# XCBMPUSche.net
KiCad netlist of a schematic drawn in Altium Designer
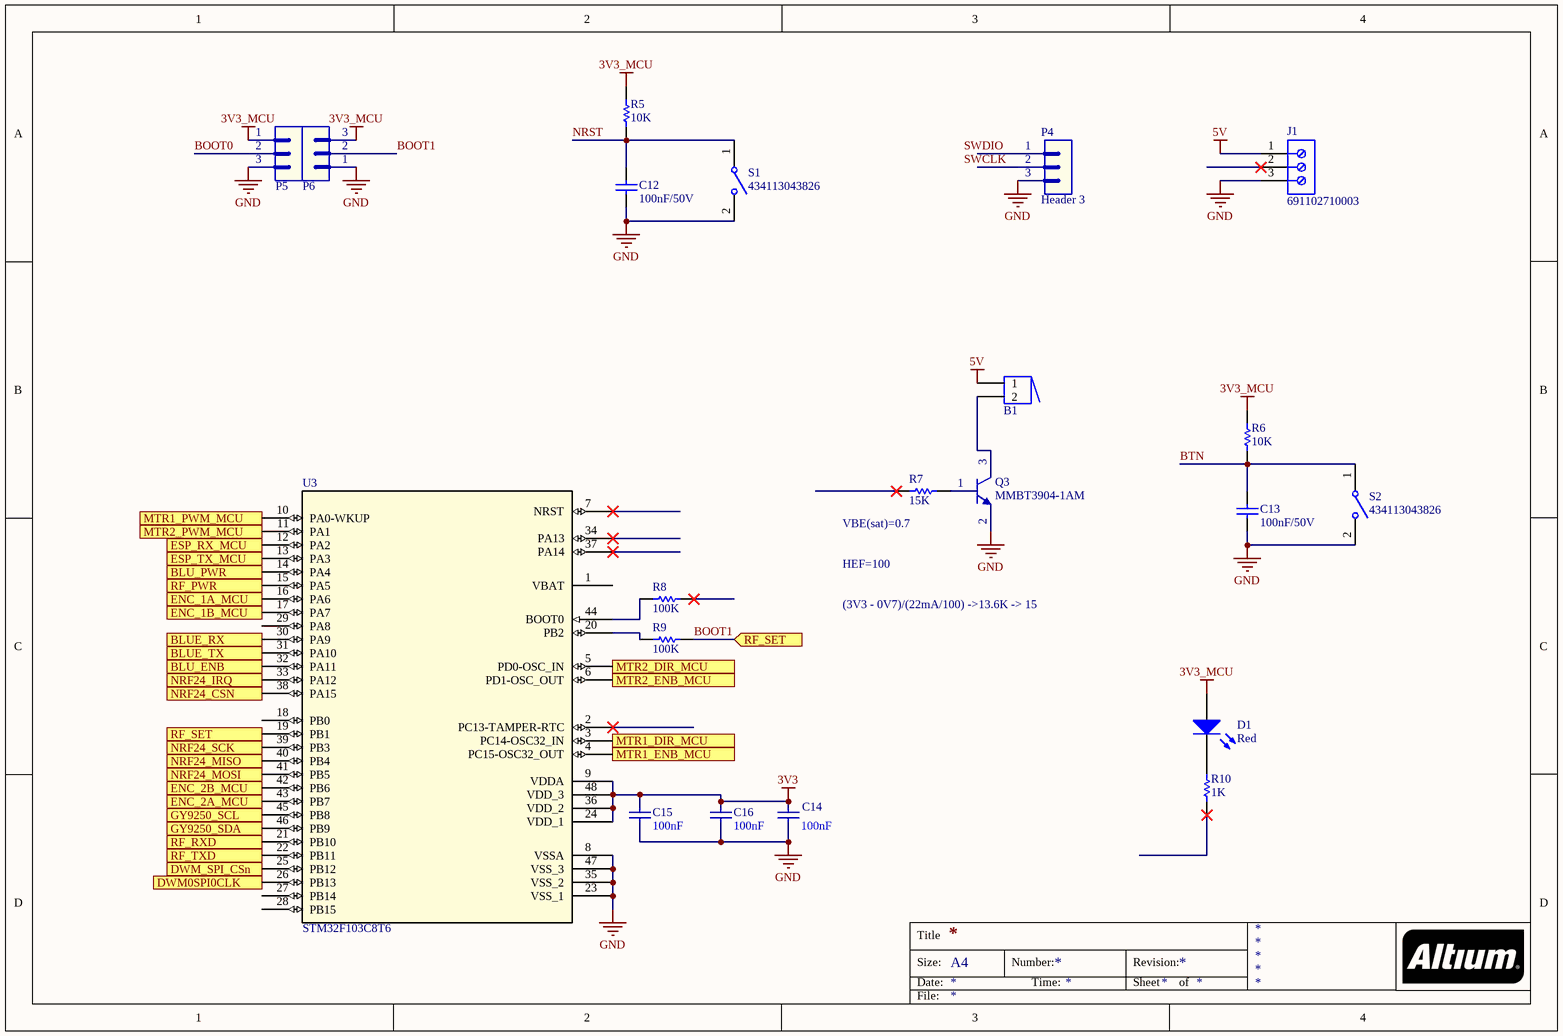
[diagram p0: XCBMPUSche.schdoc]

(export (version "E")
  (design (tool "Eeschema 10.0.6"))
  (components
    (comp (ref "B1")
      (value "Buzzer")
      (footprint "BUZZER")
      (libsource (lib "PIF_Schematic_Lib") (part "Buzzer"))
    )
    (comp (ref "C12")
      (value "100nF/50V")
      (footprint "CAP-SM-0805")
      (description "CAP CER 0.1UF 50V Y5V 0805")
      (fields
        (field (name "MANUFACTURER") "Samsung Electro-Mechanics")
        (field (name "MANUFACTURER PART NUMBER") "CL21F104ZBCNNNC")
      )
      (libsource (lib "Capacitor") (part "Cap-100nF-50V-0805"))
    )
    (comp (ref "C13")
      (value "100nF/50V")
      (footprint "CAP-SM-0805")
      (description "CAP CER 0.1UF 50V Y5V 0805")
      (fields
        (field (name "MANUFACTURER") "Samsung Electro-Mechanics")
        (field (name "MANUFACTURER PART NUMBER") "CL21F104ZBCNNNC")
      )
      (libsource (lib "Capacitor") (part "Cap-100nF-50V-0805"))
    )
    (comp (ref "C14")
      (value "100nF")
      (footprint "CN1")
      (description "Capacitor")
      (fields (field (name "Comment") "Cap Non-Pol"))
      (libsource (lib "Capacitor-TH") (part "Cap-TH-NonPol"))
    )
    (comp (ref "C15")
      (value "100nF")
      (footprint "CN1")
      (description "Capacitor")
      (fields (field (name "Comment") "Cap Non-Pol"))
      (libsource (lib "Capacitor-TH") (part "Cap-TH-NonPol"))
    )
    (comp (ref "C16")
      (value "100nF")
      (footprint "CN1")
      (description "Capacitor")
      (fields (field (name "Comment") "Cap Non-Pol"))
      (libsource (lib "Capacitor-TH") (part "Cap-TH-NonPol"))
    )
    (comp (ref "D1")
      (value "Red")
      (footprint "LED-3mm")
      (description "LED RED CLEAR T-1 T/H")
      (fields
        (field (name "MANUFACTURER") "Kingbright")
        (field (name "MANUFACTURER PART NUMBER") "WP710A10SEC/J3")
      )
      (libsource (lib "LED") (part "LED-RED-TH-3mm"))
    )
    (comp (ref "J1")
      (value "691102710003")
      (footprint "691102710003")
      (description "WR-TBL Serie 102 Horizontal Entry Modular, Pressure Clamp, pitch 5mm, 3p")
      (fields (field (name "PUBLISHER") "Wurth Elektronik"))
      (libsource (lib "691101710002_Altium_WR-TBL_rev19a") (part "691102710003"))
    )
    (comp (ref "P4")
      (value "Header 3")
      (footprint "JP3")
      (description "Header, 3-Pin")
      (fields (field (name "PUBLISHER") "Altium Limited"))
      (libsource (lib "") (part "Header 3_1"))
    )
    (comp (ref "P5")
      (value "Header 3")
      (footprint "JP3")
      (description "Header, 3-Pin")
      (fields (field (name "PUBLISHER") "Altium Limited"))
      (libsource (lib "") (part "Header 3_1"))
    )
    (comp (ref "P6")
      (value "Header 3")
      (footprint "JP3")
      (description "Header, 3-Pin")
      (fields (field (name "PUBLISHER") "Altium Limited"))
      (libsource (lib "PIF_C16_lib") (part "Header 3"))
    )
    (comp (ref "Q3")
      (value "MMBT3904-1AM")
      (footprint "SOT23_NEX")
      (libsource (lib "BJT") (part "MMBT3904-1AM"))
    )
    (comp (ref "R5")
      (value "10K")
      (footprint "Resistor:RES-SM-0805")
      (description "RES 10K OHM 1% 1/4W 0805")
      (fields
        (field (name "MANUFACTURER") "Stackpole Electronics Inc")
        (field (name "MANUFACTURER PART NUMBER") "RNCP0805FTD10K0")
      )
      (libsource (lib "Resistor") (part "Res-10k-0805"))
    )
    (comp (ref "R6")
      (value "10K")
      (footprint "Resistor:RES-SM-0805")
      (description "RES 10K OHM 1% 1/4W 0805")
      (fields
        (field (name "MANUFACTURER") "Stackpole Electronics Inc")
        (field (name "MANUFACTURER PART NUMBER") "RNCP0805FTD10K0")
      )
      (libsource (lib "Resistor") (part "Res-10k-0805"))
    )
    (comp (ref "R7")
      (value "15K")
      (footprint "Resistor:RES-SM-0805")
      (description "RES 15K OHM 1% 1/4W 0805")
      (fields
        (field (name "MANUFACTURER") "TE Connectivity Passive Product")
        (field (name "MANUFACTURER PART NUMBER") "CRGCQ0805F15K")
      )
      (libsource (lib "Resistor") (part "Res-15K-0805"))
    )
    (comp (ref "R8")
      (value "100K")
      (footprint "Resistor:RES-SM-0805")
      (description "RES 0 OHM JUMPER 0805")
      (fields
        (field (name "MANUFACTURER") "Vishay Dale")
        (field (name "MANUFACTURER PART NUMBER") "WSL080500000ZEA9")
      )
      (libsource (lib "Resistor") (part "Res-100K-0805"))
    )
    (comp (ref "R9")
      (value "100K")
      (footprint "Resistor:RES-SM-0805")
      (description "RES 0 OHM JUMPER 0805")
      (fields
        (field (name "MANUFACTURER") "Vishay Dale")
        (field (name "MANUFACTURER PART NUMBER") "WSL080500000ZEA9")
      )
      (libsource (lib "Resistor") (part "Res-100K-0805"))
    )
    (comp (ref "R10")
      (value "1K")
      (footprint "Resistor:RES-SM-0805")
      (description "RES 1K OHM 1% 1/4W 0805")
      (fields
        (field (name "MANUFACTURER") "Stackpole Electronics Inc")
        (field (name "MANUFACTURER PART NUMBER") "RNCP0805FTD1K00")
      )
      (libsource (lib "Resistor") (part "Res-1K-0805"))
    )
    (comp (ref "S1")
      (value "434113043826")
      (footprint "434113043826")
      (description "WS-TASV J-Bend SMT Tact Switch 6x3.5mm, height 4.3mm, 260gf")
      (fields (field (name "PUBLISHER") "Wurth Elektronik"))
      (libsource (lib "434113043826_Altium_WS-TASV_rev20a") (part "434113043826"))
    )
    (comp (ref "S2")
      (value "434113043826")
      (footprint "434113043826")
      (description "WS-TASV J-Bend SMT Tact Switch 6x3.5mm, height 4.3mm, 260gf")
      (fields (field (name "PUBLISHER") "Wurth Elektronik"))
      (libsource (lib "434113043826_Altium_WS-TASV_rev20a") (part "434113043826"))
    )
    (comp (ref "U3")
      (value "STM32F103C8T6")
      (footprint "STM32F103C8T6")
      (description "No Description Available")
      (fields (field (name "COPYRIGHT") "Copyright (C) 2018 Accelerated Designs. All rights reserved"))
      (libsource (lib "Bai1") (part "STM32F103C8T6"))
    )
  )
  (nets
    (net (code "1") (name "/BLUE_RX") (class "Default")
      (node (ref "U3") (pin "30") (pinfunction "PA9_30") (pintype "bidirectional"))
    )
    (net (code "2") (name "/BLUE_TX") (class "Default")
      (node (ref "U3") (pin "31") (pinfunction "PA10_31") (pintype "bidirectional"))
    )
    (net (code "3") (name "/BLU_ENB") (class "Default")
      (node (ref "U3") (pin "32") (pinfunction "PA11_32") (pintype "bidirectional"))
    )
    (net (code "4") (name "/BLU_PWR") (class "Default")
      (node (ref "U3") (pin "14") (pinfunction "PA4_14") (pintype "bidirectional"))
    )
    (net (code "5") (name "/BOOT0") (class "Default")
      (node (ref "P5") (pin "2") (pinfunction "2_2") (pintype "passive"))
    )
    (net (code "6") (name "/BOOT1") (class "Default")
      (node (ref "P6") (pin "2") (pinfunction "2_2") (pintype "passive"))
      (node (ref "R9") (pin "2") (pinfunction "2_2") (pintype "passive"))
      (node (ref "U3") (pin "19") (pinfunction "PB1_19") (pintype "bidirectional"))
    )
    (net (code "7") (name "/BTN") (class "Default")
      (node (ref "C13") (pin "2") (pinfunction "2_2") (pintype "passive"))
      (node (ref "R6") (pin "1") (pinfunction "1_1") (pintype "passive"))
      (node (ref "S2") (pin "1") (pinfunction "1_1") (pintype "passive"))
    )
    (net (code "8") (name "/DWM0SPI0CLK") (class "Default")
      (node (ref "U3") (pin "26") (pinfunction "PB13_26") (pintype "bidirectional"))
    )
    (net (code "9") (name "/DWM_SPI_CSn") (class "Default")
      (node (ref "U3") (pin "25") (pinfunction "PB12_25") (pintype "bidirectional"))
    )
    (net (code "10") (name "/ENC_1A_MCU") (class "Default")
      (node (ref "U3") (pin "16") (pinfunction "PA6_16") (pintype "bidirectional"))
    )
    (net (code "11") (name "/ENC_1B_MCU") (class "Default")
      (node (ref "U3") (pin "17") (pinfunction "PA7_17") (pintype "bidirectional"))
    )
    (net (code "12") (name "/ENC_2A_MCU") (class "Default")
      (node (ref "U3") (pin "43") (pinfunction "PB7_43") (pintype "bidirectional"))
    )
    (net (code "13") (name "/ENC_2B_MCU") (class "Default")
      (node (ref "U3") (pin "42") (pinfunction "PB6_42") (pintype "bidirectional"))
    )
    (net (code "14") (name "/ESP_RX_MCU") (class "Default")
      (node (ref "U3") (pin "12") (pinfunction "PA2_12") (pintype "bidirectional"))
    )
    (net (code "15") (name "/ESP_TX_MCU") (class "Default")
      (node (ref "U3") (pin "13") (pinfunction "PA3_13") (pintype "bidirectional"))
    )
    (net (code "16") (name "/GY9250_SCL") (class "Default")
      (node (ref "U3") (pin "45") (pinfunction "PB8_45") (pintype "bidirectional"))
    )
    (net (code "17") (name "/GY9250_SDA") (class "Default")
      (node (ref "U3") (pin "46") (pinfunction "PB9_46") (pintype "bidirectional"))
    )
    (net (code "18") (name "/MTR1_DIR_MCU") (class "Default")
      (node (ref "U3") (pin "3") (pinfunction "PC14-OSC32_IN_3") (pintype "bidirectional"))
    )
    (net (code "19") (name "/MTR1_ENB_MCU") (class "Default")
      (node (ref "U3") (pin "4") (pinfunction "PC15-OSC32_OUT_4") (pintype "bidirectional"))
    )
    (net (code "20") (name "/MTR1_PWM_MCU") (class "Default")
      (node (ref "U3") (pin "10") (pinfunction "PA0-WKUP_10") (pintype "bidirectional"))
    )
    (net (code "21") (name "/MTR2_DIR_MCU") (class "Default")
      (node (ref "U3") (pin "5") (pinfunction "PD0-OSC_IN_5") (pintype "bidirectional"))
    )
    (net (code "22") (name "/MTR2_ENB_MCU") (class "Default")
      (node (ref "U3") (pin "6") (pinfunction "PD1-OSC_OUT_6") (pintype "bidirectional"))
    )
    (net (code "23") (name "/MTR2_PWM_MCU") (class "Default")
      (node (ref "U3") (pin "11") (pinfunction "PA1_11") (pintype "bidirectional"))
    )
    (net (code "24") (name "/NRF24_CSN") (class "Default")
      (node (ref "U3") (pin "38") (pinfunction "PA15_38") (pintype "bidirectional"))
    )
    (net (code "25") (name "/NRF24_IRQ") (class "Default")
      (node (ref "U3") (pin "33") (pinfunction "PA12_33") (pintype "bidirectional"))
    )
    (net (code "26") (name "/NRF24_MISO") (class "Default")
      (node (ref "U3") (pin "40") (pinfunction "PB4_40") (pintype "bidirectional"))
    )
    (net (code "27") (name "/NRF24_MOSI") (class "Default")
      (node (ref "U3") (pin "41") (pinfunction "PB5_41") (pintype "bidirectional"))
    )
    (net (code "28") (name "/NRF24_SCK") (class "Default")
      (node (ref "U3") (pin "39") (pinfunction "PB3_39") (pintype "bidirectional"))
    )
    (net (code "29") (name "/NRST") (class "Default")
      (node (ref "C12") (pin "2") (pinfunction "2_2") (pintype "passive"))
      (node (ref "R5") (pin "1") (pinfunction "1_1") (pintype "passive"))
      (node (ref "S1") (pin "1") (pinfunction "1_1") (pintype "passive"))
    )
    (net (code "30") (name "/RF_PWR") (class "Default")
      (node (ref "U3") (pin "15") (pinfunction "PA5_15") (pintype "bidirectional"))
    )
    (net (code "31") (name "/RF_RXD") (class "Default")
      (node (ref "U3") (pin "21") (pinfunction "PB10_21") (pintype "bidirectional"))
    )
    (net (code "32") (name "/RF_TXD") (class "Default")
      (node (ref "U3") (pin "22") (pinfunction "PB11_22") (pintype "bidirectional"))
    )
    (net (code "35") (name "3V3") (class "Default")
      (node (ref "C14") (pin "2") (pinfunction "2_2") (pintype "passive"))
      (node (ref "C15") (pin "2") (pinfunction "2_2") (pintype "passive"))
      (node (ref "C16") (pin "2") (pinfunction "2_2") (pintype "passive"))
      (node (ref "U3") (pin "24") (pinfunction "VDD_1_24") (pintype "passive"))
      (node (ref "U3") (pin "36") (pinfunction "VDD_2_36") (pintype "power_in"))
      (node (ref "U3") (pin "48") (pinfunction "VDD_3_48") (pintype "passive"))
      (node (ref "U3") (pin "9") (pinfunction "VDDA_9") (pintype "passive"))
    )
    (net (code "36") (name "3V3_MCU") (class "Default")
      (node (ref "D1") (pin "1") (pinfunction "A_1") (pintype "passive"))
      (node (ref "P5") (pin "1") (pinfunction "1_1") (pintype "passive"))
      (node (ref "P6") (pin "3") (pinfunction "3_3") (pintype "passive"))
      (node (ref "R5") (pin "2") (pinfunction "2_2") (pintype "passive"))
      (node (ref "R6") (pin "2") (pinfunction "2_2") (pintype "passive"))
    )
    (net (code "37") (name "5V") (class "Default")
      (node (ref "B1") (pin "1") (pinfunction "1_1") (pintype "passive"))
      (node (ref "J1") (pin "1") (pinfunction "1_1") (pintype "passive"))
    )
    (net (code "38") (name "GND") (class "Default")
      (node (ref "C12") (pin "1") (pinfunction "1_1") (pintype "passive"))
      (node (ref "C13") (pin "1") (pinfunction "1_1") (pintype "passive"))
      (node (ref "C14") (pin "1") (pinfunction "1_1") (pintype "passive"))
      (node (ref "C15") (pin "1") (pinfunction "1_1") (pintype "passive"))
      (node (ref "C16") (pin "1") (pinfunction "1_1") (pintype "passive"))
      (node (ref "J1") (pin "3") (pinfunction "3_3") (pintype "passive"))
      (node (ref "P4") (pin "3") (pinfunction "3_3") (pintype "passive"))
      (node (ref "P5") (pin "3") (pinfunction "3_3") (pintype "passive"))
      (node (ref "P6") (pin "1") (pinfunction "1_1") (pintype "passive"))
      (node (ref "Q3") (pin "2") (pinfunction "E_2") (pintype "passive"))
      (node (ref "S1") (pin "2") (pinfunction "2_2") (pintype "passive"))
      (node (ref "S2") (pin "2") (pinfunction "2_2") (pintype "passive"))
      (node (ref "U3") (pin "23") (pinfunction "VSS_1_23") (pintype "passive"))
      (node (ref "U3") (pin "35") (pinfunction "VSS_2_35") (pintype "passive"))
      (node (ref "U3") (pin "47") (pinfunction "VSS_3_47") (pintype "passive"))
      (node (ref "U3") (pin "8") (pinfunction "VSSA_8") (pintype "passive"))
    )
    (net (code "39") (name "Net-(D1-K)") (class "Default")
      (node (ref "D1") (pin "2") (pinfunction "K_2") (pintype "passive"))
      (node (ref "R10") (pin "2") (pinfunction "2_2") (pintype "passive"))
    )
    (net (code "40") (name "Net-(Q3-B)") (class "Default")
      (node (ref "Q3") (pin "1") (pinfunction "B_1") (pintype "passive"))
      (node (ref "R7") (pin "2") (pinfunction "2_2") (pintype "passive"))
    )
    (net (code "41") (name "Net-(Q3-C)") (class "Default")
      (node (ref "B1") (pin "2") (pinfunction "2_2") (pintype "passive"))
      (node (ref "Q3") (pin "3") (pinfunction "C_3") (pintype "passive"))
    )
    (net (code "42") (name "Net-(U3-BOOT0)") (class "Default")
      (node (ref "R8") (pin "1") (pinfunction "1_1") (pintype "passive"))
      (node (ref "U3") (pin "44") (pinfunction "BOOT0_44") (pintype "input"))
    )
    (net (code "43") (name "Net-(U3-PB2)") (class "Default")
      (node (ref "R9") (pin "1") (pinfunction "1_1") (pintype "passive"))
      (node (ref "U3") (pin "20") (pinfunction "PB2_20") (pintype "bidirectional"))
    )
    (net (code "44") (name "unconnected-(J1-Pad2)") (class "Default")
      (node (ref "J1") (pin "2") (pinfunction "2_2") (pintype "passive+no_connect"))
    )
    (net (code "45") (name "unconnected-(P4-Pad1)") (class "Default")
      (node (ref "P4") (pin "1") (pinfunction "1_1") (pintype "passive"))
    )
    (net (code "46") (name "unconnected-(P4-Pad2)") (class "Default")
      (node (ref "P4") (pin "2") (pinfunction "2_2") (pintype "passive"))
    )
    (net (code "47") (name "unconnected-(R7-Pad1)") (class "Default")
      (node (ref "R7") (pin "1") (pinfunction "1_1") (pintype "passive+no_connect"))
    )
    (net (code "48") (name "unconnected-(R8-Pad2)") (class "Default")
      (node (ref "R8") (pin "2") (pinfunction "2_2") (pintype "passive+no_connect"))
    )
    (net (code "49") (name "unconnected-(R10-Pad1)") (class "Default")
      (node (ref "R10") (pin "1") (pinfunction "1_1") (pintype "passive+no_connect"))
    )
    (net (code "50") (name "unconnected-(U3-NRST-Pad7)") (class "Default")
      (node (ref "U3") (pin "7") (pinfunction "NRST_7") (pintype "bidirectional+no_connect"))
    )
    (net (code "51") (name "unconnected-(U3-PA8-Pad29)") (class "Default")
      (node (ref "U3") (pin "29") (pinfunction "PA8_29") (pintype "bidirectional"))
    )
    (net (code "52") (name "unconnected-(U3-PA13-Pad34)") (class "Default")
      (node (ref "U3") (pin "34") (pinfunction "PA13_34") (pintype "bidirectional+no_connect"))
    )
    (net (code "53") (name "unconnected-(U3-PA14-Pad37)") (class "Default")
      (node (ref "U3") (pin "37") (pinfunction "PA14_37") (pintype "bidirectional+no_connect"))
    )
    (net (code "54") (name "unconnected-(U3-PB0-Pad18)") (class "Default")
      (node (ref "U3") (pin "18") (pinfunction "PB0_18") (pintype "bidirectional"))
    )
    (net (code "55") (name "unconnected-(U3-PB14-Pad27)") (class "Default")
      (node (ref "U3") (pin "27") (pinfunction "PB14_27") (pintype "bidirectional"))
    )
    (net (code "56") (name "unconnected-(U3-PB15-Pad28)") (class "Default")
      (node (ref "U3") (pin "28") (pinfunction "PB15_28") (pintype "bidirectional"))
    )
    (net (code "57") (name "unconnected-(U3-PC13-TAMPER-RTC-Pad2)") (class "Default")
      (node (ref "U3") (pin "2") (pinfunction "PC13-TAMPER-RTC_2") (pintype "bidirectional+no_connect"))
    )
    (net (code "58") (name "unconnected-(U3-VBAT-Pad1)") (class "Default")
      (node (ref "U3") (pin "1") (pinfunction "VBAT_1") (pintype "power_in"))
    )
  )
)
